# Magnetometer_Channel.net
KiCad netlist of a schematic drawn in Altium Designer
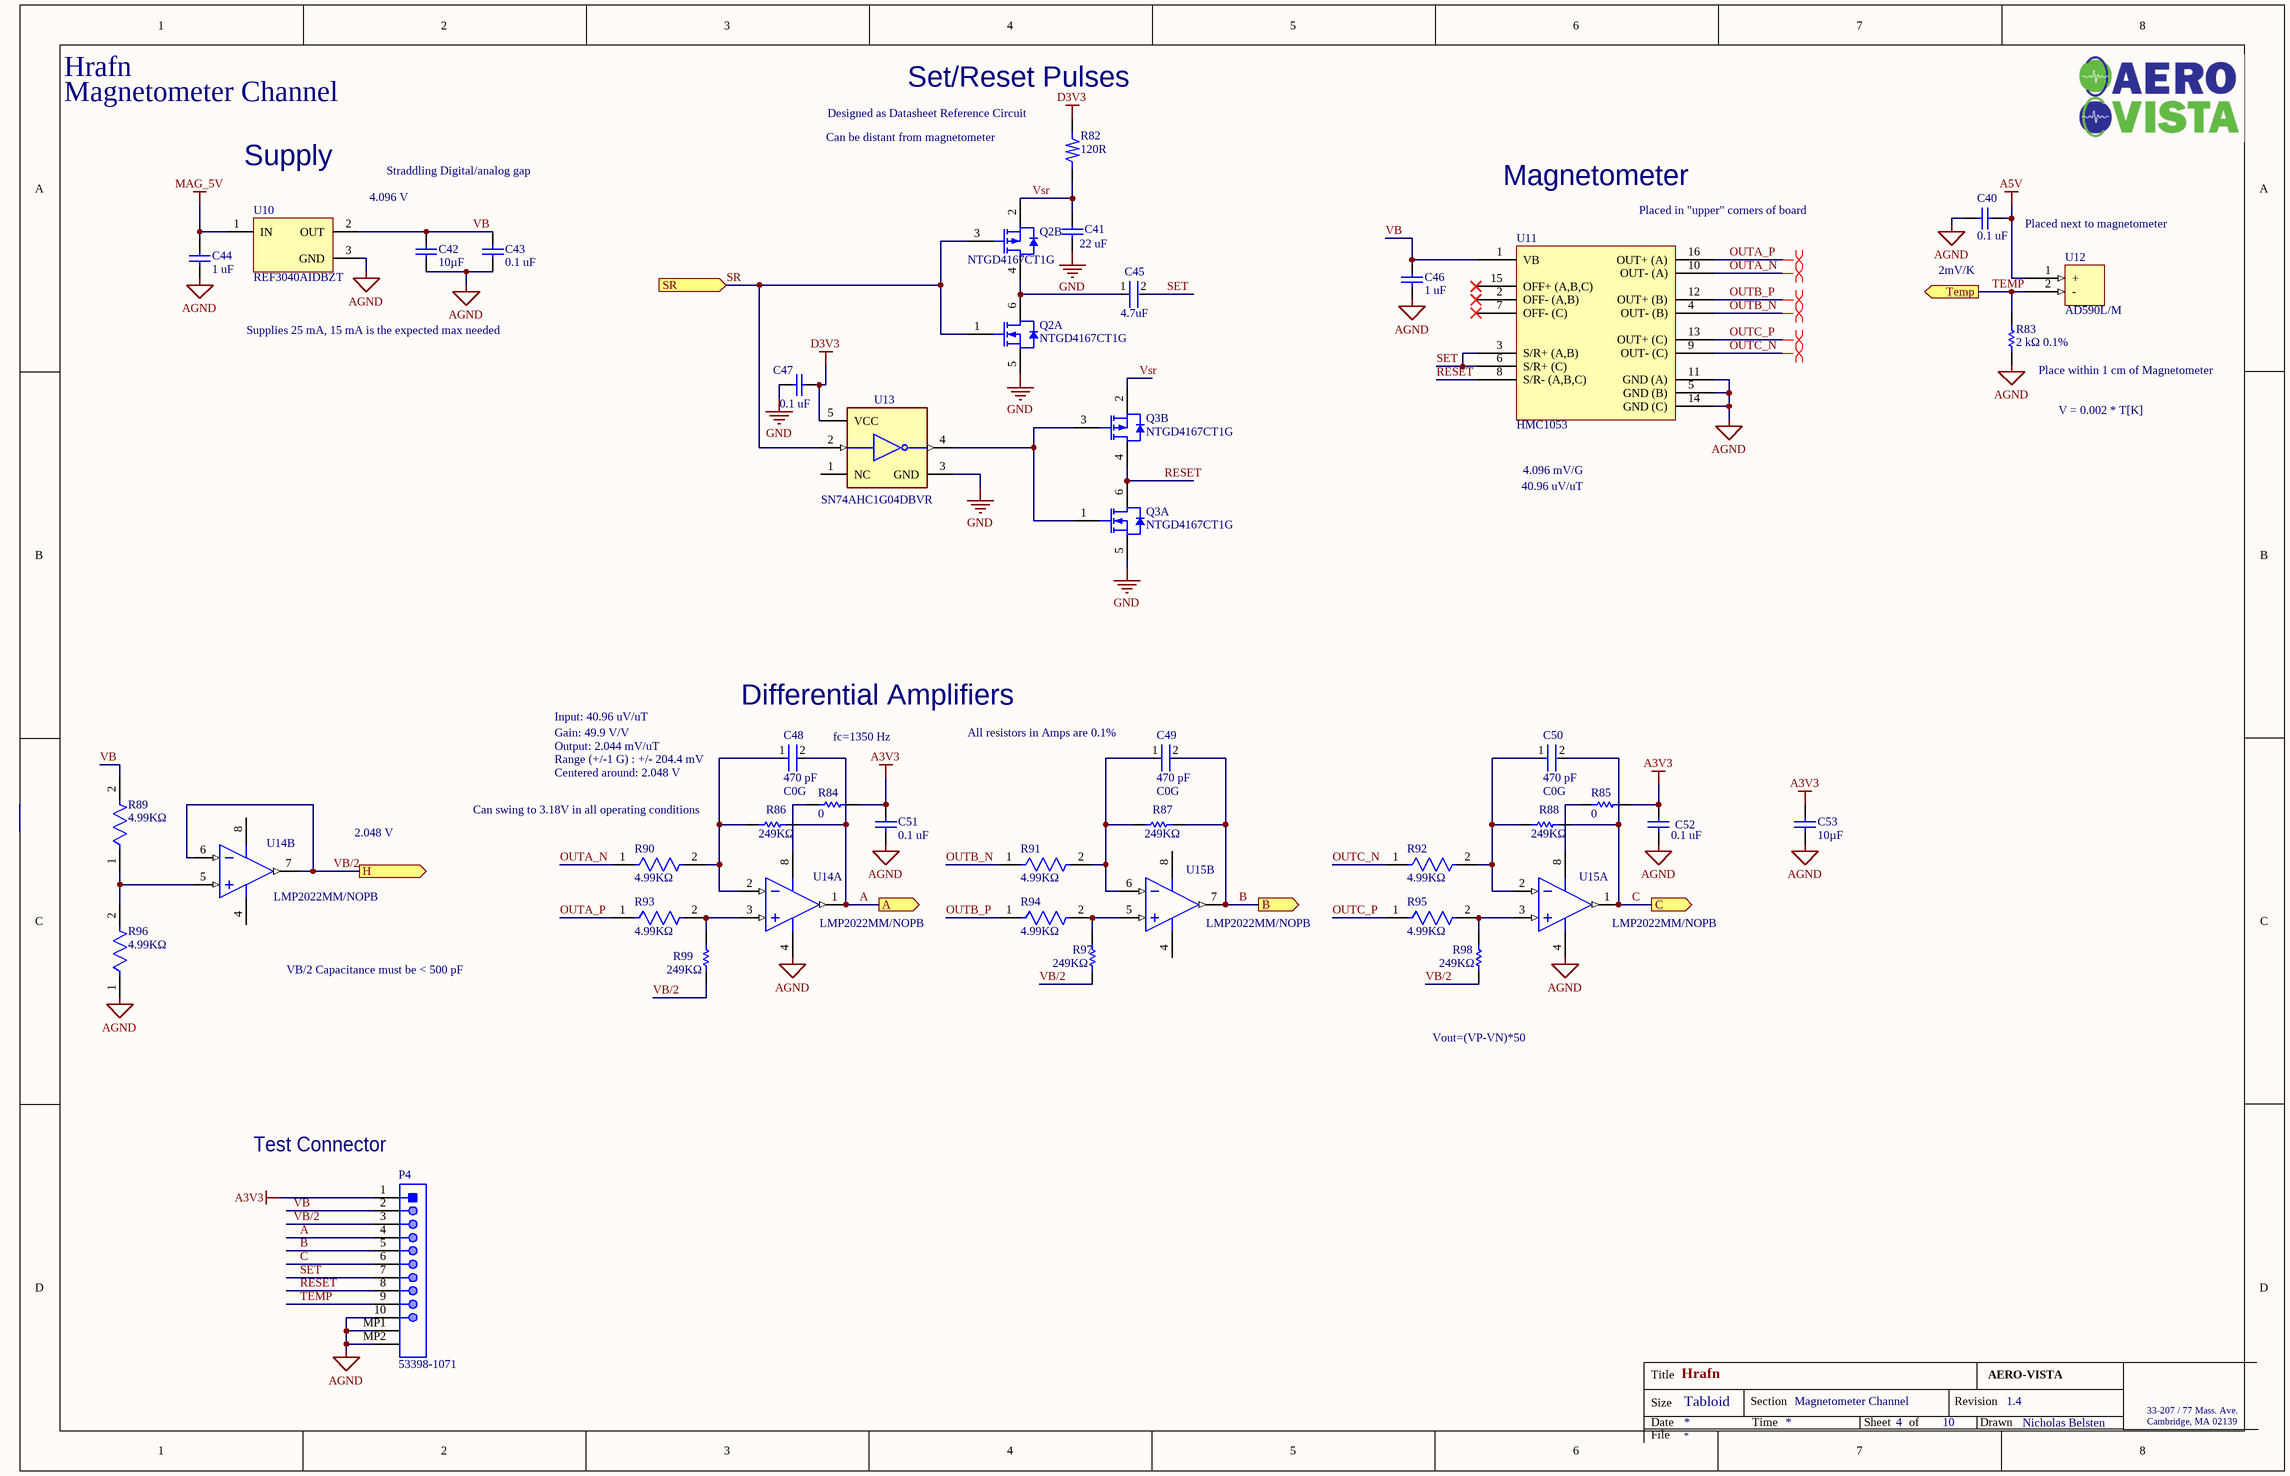
[diagram p0: Magnetometer_Channel.SchDoc]

(export (version "E")
  (design (tool "Eeschema 10.0.6"))
  (components
    (comp (ref "C40")
      (value "0.1 uF")
      (footprint "CAPC0402(1005)60_L")
      (description "CAP 100nF 16V ±5% 0402 (1005 Metric) Thickness 0.6mm SMD")
      (fields (field (name "TOLERANCE") "Â±5%"))
      (libsource (lib "Altium Content Vault") (part "CAP"))
    )
    (comp (ref "C41")
      (value "GRM219R61A226MEA0D")
      (footprint "CAPC2013X95X45LL15T25")
      (fields (field (name "MANUFACTURER") "Murata") (field (name "CAPACITANCE") "22 uF"))
      (libsource (lib "Altium Content Vault") (part "CAP"))
    )
    (comp (ref "C42")
      (value "EMK107BBJ106MA-T")
      (footprint "CAPC1608X100X35LL20T25")
      (description "Chip Capacitor, 10 uF, +/- 20%, 16 V, -55 to 85 degC, 0603 (1608 Metric), RoHS, Tape and Reel")
      (fields
        (field (name "CAPACITANCE") "10µF")
        (field (name "MANUFACTURER") "Taiyo Yuden")
        (field (name "TOLERANCE") "±20%")
      )
      (libsource (lib "Altium Content Vault") (part "CAP-NP-2"))
    )
    (comp (ref "C43")
      (value "0.1 uF")
      (footprint "CAPC0402(1005)60_L")
      (description "CAP 100nF 16V ±5% 0402 (1005 Metric) Thickness 0.6mm SMD")
      (fields (field (name "TOLERANCE") "Â±5%"))
      (libsource (lib "Altium Content Vault") (part "CAP"))
    )
    (comp (ref "C44")
      (value "1 uF")
      (footprint "CAPC1005X60X30NL05T10")
      (fields (field (name "PART NUMBER") "C0402C105M8PACTU") (field (name "MANUFACTURER") "Kemet"))
      (libsource (lib "Altium Content Vault") (part "CAP"))
    )
    (comp (ref "C45")
      (value "GRM188R6YA475KE15D")
      (footprint "FP-GRM188-0_2-IPC_C")
      (description "Chip Multilayer Ceramic Capacitors for General Purpose, 0603, 4.7uF, X5R, 15%, 10%, 35V")
      (fields
        (field (name "CAPACITANCE") "4.7uF")
        (field (name "VOLTAGE") "35V")
        (field (name "TOLERANCE") "10%")
      )
      (libsource (lib "Altium Content Vault") (part "11868f565c42a9108669ba33697ecf6"))
    )
    (comp (ref "C46")
      (value "1 uF")
      (footprint "CAPC1005X60X30NL05T10")
      (fields (field (name "PART NUMBER") "C0402C105M8PACTU") (field (name "MANUFACTURER") "Kemet"))
      (libsource (lib "Altium Content Vault") (part "CAP"))
    )
    (comp (ref "C47")
      (value "0.1 uF")
      (footprint "CAPC0402(1005)60_L")
      (description "CAP 100nF 16V ±5% 0402 (1005 Metric) Thickness 0.6mm SMD")
      (fields (field (name "TOLERANCE") "Â±5%"))
      (libsource (lib "Altium Content Vault") (part "CAP"))
    )
    (comp (ref "C48")
      (value "C0402C471F5GACTU")
      (footprint "FP-C0402-BB-MFG")
      (description "CAP CER 470PF 50V NP0 0402")
      (fields
        (field (name "CAPACITANCE") "470 pF")
        (field (name "MANUFACTURER") "Kemet")
        (field (name "TOLERANCE") "0.01")
        (field (name "TEMPERATURE CHARACTERISTIC") "C0G")
      )
      (libsource (lib "Altium Content Vault") (part "b4654b650e69147ec39a6b967a45e02"))
    )
    (comp (ref "C49")
      (value "C0402C471F5GACTU")
      (footprint "FP-C0402-BB-MFG")
      (description "CAP CER 470PF 50V NP0 0402")
      (fields
        (field (name "CAPACITANCE") "470 pF")
        (field (name "MANUFACTURER") "Kemet")
        (field (name "TOLERANCE") "0.01")
        (field (name "TEMPERATURE CHARACTERISTIC") "C0G")
      )
      (libsource (lib "Altium Content Vault") (part "b4654b650e69147ec39a6b967a45e02"))
    )
    (comp (ref "C50")
      (value "C0402C471F5GACTU")
      (footprint "FP-C0402-BB-MFG")
      (description "CAP CER 470PF 50V NP0 0402")
      (fields
        (field (name "CAPACITANCE") "470 pF")
        (field (name "MANUFACTURER") "Kemet")
        (field (name "TOLERANCE") "0.01")
        (field (name "TEMPERATURE CHARACTERISTIC") "C0G")
      )
      (libsource (lib "Altium Content Vault") (part "b4654b650e69147ec39a6b967a45e02"))
    )
    (comp (ref "C51")
      (value "0.1 uF")
      (footprint "CAPC0402(1005)60_L")
      (description "CAP 100nF 16V ±5% 0402 (1005 Metric) Thickness 0.6mm SMD")
      (fields (field (name "TOLERANCE") "Â±5%"))
      (libsource (lib "Altium Content Vault") (part "CAP"))
    )
    (comp (ref "C52")
      (value "0.1 uF")
      (footprint "CAPC0402(1005)60_L")
      (description "CAP 100nF 16V ±5% 0402 (1005 Metric) Thickness 0.6mm SMD")
      (fields (field (name "TOLERANCE") "Â±5%"))
      (libsource (lib "Altium Content Vault") (part "CAP"))
    )
    (comp (ref "C53")
      (value "EMK107BBJ106MA-T")
      (footprint "CAPC1608X100X35LL20T25")
      (description "Chip Capacitor, 10 uF, +/- 20%, 16 V, -55 to 85 degC, 0603 (1608 Metric), RoHS, Tape and Reel")
      (fields
        (field (name "CAPACITANCE") "10µF")
        (field (name "MANUFACTURER") "Taiyo Yuden")
        (field (name "TOLERANCE") "±20%")
      )
      (libsource (lib "Altium Content Vault") (part "CAP-NP-2"))
    )
    (comp (ref "P4")
      (value "53398-1071")
      (footprint "MOLX-53398-1071_V")
      (description "Male Header, Pitch 1.25 mm, 1 x 10 Position, Height 4.7 mm, -40 to 85 degC, RoHS, Tape and Reel")
      (fields (field (name "MANUFACTURER") "Molex"))
      (libsource (lib "Altium Content Vault") (part "CN-1P-2M-R10"))
    )
    (comp (ref "Q2")
      (value "NTGD4167CT1G")
      (footprint "ONSC-TSOP-6-318G-02_V")
      (description "Power MOSFET, Complementary, 30 V, +2.9 / -2.2 A, 6-Pin TSOP, Pb-Free, Tape and Reel")
      (fields (field (name "MANUFACTURER") "On Semiconductor"))
      (libsource (lib "Altium Content Vault") (part "ONSC-NTGD4167C-TSOP-6-318G-02"))
    )
    (comp (ref "Q3")
      (value "NTGD4167CT1G")
      (footprint "ONSC-TSOP-6-318G-02_V")
      (description "Power MOSFET, Complementary, 30 V, +2.9 / -2.2 A, 6-Pin TSOP, Pb-Free, Tape and Reel")
      (fields (field (name "MANUFACTURER") "On Semiconductor"))
      (libsource (lib "Altium Content Vault") (part "ONSC-NTGD4167C-TSOP-6-318G-02"))
    )
    (comp (ref "R82")
      (value "R")
      (footprint "RESC1608X08L")
      (description "ROHM - ESR03EZPJ121 - RES, AEC-Q200, THICK FILM, 120R, 5%, 0603 ROHS COMPLIANT: YES")
      (fields (field (name "TOLERANCE") "5%") (field (name "RESISTANCE") "120R"))
      (libsource (lib "Hrafn") (part "R"))
    )
    (comp (ref "R83")
      (value "2 kΩ 0.1%")
      (footprint "RESC1005X40X25LL10T10")
      (fields (field (name "MANUFACTURER") "Panasonic") (field (name "PART NUMBER") "ERA-2AEB202X"))
      (libsource (lib "Altium Content Vault") (part "RES"))
    )
    (comp (ref "R84")
      (value "0")
      (footprint "RESC1608X55X25NL10T15")
      (description "Chip Resistor, 0 Ohm, +/- 5%, 0.1 W, -55 to 155 degC, 0603 (1608 Metric), RoHS, Tape and Reel")
      (fields (field (name "TOLERANCE") "5%") (field (name "MANUFACTURER") "Yageo"))
      (libsource (lib "Altium Content Vault") (part "RES-2"))
    )
    (comp (ref "R85")
      (value "0")
      (footprint "RESC1608X55X25NL10T15")
      (description "Chip Resistor, 0 Ohm, +/- 5%, 0.1 W, -55 to 155 degC, 0603 (1608 Metric), RoHS, Tape and Reel")
      (fields (field (name "TOLERANCE") "5%") (field (name "MANUFACTURER") "Yageo"))
      (libsource (lib "Altium Content Vault") (part "RES-2"))
    )
    (comp (ref "R86")
      (value "249KΩ")
      (footprint "RESC1609X55X30LL10T20")
      (fields (field (name "PART NUMBER") "TNPW0603249KBEEA") (field (name "MANUFACTURER") "Vishay Dale"))
      (libsource (lib "Altium Content Vault") (part "RES"))
    )
    (comp (ref "R87")
      (value "249KΩ")
      (footprint "RESC1609X55X30LL10T20")
      (fields (field (name "PART NUMBER") "TNPW0603249KBEEA") (field (name "MANUFACTURER") "Vishay Dale"))
      (libsource (lib "Altium Content Vault") (part "RES"))
    )
    (comp (ref "R88")
      (value "249KΩ")
      (footprint "RESC1609X55X30LL10T20")
      (fields (field (name "PART NUMBER") "TNPW0603249KBEEA") (field (name "MANUFACTURER") "Vishay Dale"))
      (libsource (lib "Altium Content Vault") (part "RES"))
    )
    (comp (ref "R89")
      (value "4.99KΩ")
      (footprint "FP-RT0603-IPC_B")
      (description "RES SMD 4.99K OHM 0.1% 1/10W")
      (fields
        (field (name "MANUFACTURER PART NUMBER") "RT0603BRE074K99L")
        (field (name "OCTOPART") "https://octopart.com/rt0603bre074k99l-yageo-1445653")
      )
      (libsource (lib "Altium Content Vault") (part "1029c3af85768c4190bb7ad29bc67b5"))
    )
    (comp (ref "R90")
      (value "4.99KΩ")
      (footprint "FP-RT0603-MFG")
      (description "RES SMD 4.99K OHM 0.1% 1/10W")
      (fields
        (field (name "MANUFACTURER PART NUMBER") "RT0603BRE074K99L")
        (field (name "OCTOPART") "https://octopart.com/rt0603bre074k99l-yageo-1445653")
      )
      (libsource (lib "Altium Content Vault") (part "1029c3af85768c4190bb7ad29bc67b5"))
    )
    (comp (ref "R91")
      (value "4.99KΩ")
      (footprint "FP-RT0603-IPC_B")
      (description "RES SMD 4.99K OHM 0.1% 1/10W")
      (fields
        (field (name "MANUFACTURER PART NUMBER") "RT0603BRE074K99L")
        (field (name "OCTOPART") "https://octopart.com/rt0603bre074k99l-yageo-1445653")
      )
      (libsource (lib "Altium Content Vault") (part "1029c3af85768c4190bb7ad29bc67b5"))
    )
    (comp (ref "R92")
      (value "4.99KΩ")
      (footprint "FP-RT0603-IPC_B")
      (description "RES SMD 4.99K OHM 0.1% 1/10W")
      (fields
        (field (name "MANUFACTURER PART NUMBER") "RT0603BRE074K99L")
        (field (name "OCTOPART") "https://octopart.com/rt0603bre074k99l-yageo-1445653")
      )
      (libsource (lib "Altium Content Vault") (part "1029c3af85768c4190bb7ad29bc67b5"))
    )
    (comp (ref "R93")
      (value "4.99KΩ")
      (footprint "FP-RT0603-IPC_B")
      (description "RES SMD 4.99K OHM 0.1% 1/10W")
      (fields
        (field (name "MANUFACTURER PART NUMBER") "RT0603BRE074K99L")
        (field (name "OCTOPART") "https://octopart.com/rt0603bre074k99l-yageo-1445653")
      )
      (libsource (lib "Altium Content Vault") (part "1029c3af85768c4190bb7ad29bc67b5"))
    )
    (comp (ref "R94")
      (value "4.99KΩ")
      (footprint "FP-RT0603-IPC_B")
      (description "RES SMD 4.99K OHM 0.1% 1/10W")
      (fields
        (field (name "MANUFACTURER PART NUMBER") "RT0603BRE074K99L")
        (field (name "OCTOPART") "https://octopart.com/rt0603bre074k99l-yageo-1445653")
      )
      (libsource (lib "Altium Content Vault") (part "1029c3af85768c4190bb7ad29bc67b5"))
    )
    (comp (ref "R95")
      (value "4.99KΩ")
      (footprint "FP-RT0603-IPC_B")
      (description "RES SMD 4.99K OHM 0.1% 1/10W")
      (fields
        (field (name "MANUFACTURER PART NUMBER") "RT0603BRE074K99L")
        (field (name "OCTOPART") "https://octopart.com/rt0603bre074k99l-yageo-1445653")
      )
      (libsource (lib "Altium Content Vault") (part "1029c3af85768c4190bb7ad29bc67b5"))
    )
    (comp (ref "R96")
      (value "4.99KΩ")
      (footprint "FP-RT0603-IPC_B")
      (description "RES SMD 4.99K OHM 0.1% 1/10W")
      (fields
        (field (name "MANUFACTURER PART NUMBER") "RT0603BRE074K99L")
        (field (name "OCTOPART") "https://octopart.com/rt0603bre074k99l-yageo-1445653")
      )
      (libsource (lib "Altium Content Vault") (part "1029c3af85768c4190bb7ad29bc67b5"))
    )
    (comp (ref "R97")
      (value "249KΩ")
      (footprint "RESC1609X55X30LL10T20")
      (fields (field (name "PART NUMBER") "TNPW0603249KBEEA") (field (name "MANUFACTURER") "Vishay Dale"))
      (libsource (lib "Altium Content Vault") (part "RES"))
    )
    (comp (ref "R98")
      (value "249KΩ")
      (footprint "RESC1609X55X30LL10T20")
      (fields (field (name "PART NUMBER") "TNPW0603249KBEEA") (field (name "MANUFACTURER") "Vishay Dale"))
      (libsource (lib "Altium Content Vault") (part "RES"))
    )
    (comp (ref "R99")
      (value "249KΩ")
      (footprint "RESC1609X55X30LL10T20")
      (fields (field (name "PART NUMBER") "TNPW0603249KBEEA") (field (name "MANUFACTURER") "Vishay Dale"))
      (libsource (lib "Altium Content Vault") (part "RES"))
    )
    (comp (ref "U10")
      (value "REF3040AIDBZT")
      (footprint "DBZ0003A_N")
      (fields (field (name "MANUFACTURER") "Texas Instruments"))
      (libsource (lib "Altium Content Vault") (part "TI-REF3040DBZ3"))
    )
    (comp (ref "U11") (value "HMC1053") (footprint "LCC16") (libsource (lib "MagEval") (part "HMC1053")))
    (comp (ref "U12") (value "AD590L/M") (footprint "2-FLATPAK") (libsource (lib "Hrafn") (part "AD590L/M")))
    (comp (ref "U13")
      (value "SN74AHC1G04DBVR")
      (footprint "FP-DBV0005A-MFG")
      (description "IC INVERTER 1CH 1-INP SOT23-5")
      (fields
        (field (name "MANUFACTURER") "Texas Instruments")
        (field (name "OCTOPART") "https://octopart.com/sn74ahc1g04dbvr-texas+instruments-464402")
      )
      (libsource (lib "Altium Content Vault") (part "ee34fa538168f64b6768a6ac9278744"))
    )
    (comp (ref "U14")
      (value "LMP2022MM/NOPB")
      (footprint "DGK0008A_L")
      (description "Zero Drift, Low Noise, EMI Hardened Amplifier, 8-pin Mini SOIC, Pb-Free")
      (fields (field (name "MANUFACTURER") "Texas Instruments"))
      (libsource (lib "Altium Content Vault") (part "AMP-OPA-LF353-8"))
    )
    (comp (ref "U15")
      (value "LMP2022MM/NOPB")
      (footprint "DGK0008A_L")
      (description "Zero Drift, Low Noise, EMI Hardened Amplifier, 8-pin Mini SOIC, Pb-Free")
      (fields (field (name "MANUFACTURER") "Texas Instruments"))
      (libsource (lib "Altium Content Vault") (part "AMP-OPA-LF353-8"))
    )
  )
  (nets
    (net (code "1") (name "/A") (class "Default")
      (node (ref "C48") (pin "2") (pinfunction "2_2") (pintype "passive"))
      (node (ref "P4") (pin "4") (pinfunction "4_4") (pintype "passive"))
      (node (ref "R86") (pin "2") (pinfunction "2_2") (pintype "passive"))
      (node (ref "U14") (pin "1") (pinfunction "OUTA_1") (pintype "output"))
    )
    (net (code "2") (name "/B") (class "Default")
      (node (ref "C49") (pin "2") (pinfunction "2_2") (pintype "passive"))
      (node (ref "P4") (pin "5") (pinfunction "5_5") (pintype "passive"))
      (node (ref "R87") (pin "2") (pinfunction "2_2") (pintype "passive"))
      (node (ref "U15") (pin "7") (pinfunction "OUTB_7") (pintype "output"))
    )
    (net (code "3") (name "/C") (class "Default")
      (node (ref "C50") (pin "2") (pinfunction "2_2") (pintype "passive"))
      (node (ref "P4") (pin "6") (pinfunction "6_6") (pintype "passive"))
      (node (ref "R88") (pin "2") (pinfunction "2_2") (pintype "passive"))
      (node (ref "U15") (pin "1") (pinfunction "OUTA_1") (pintype "output"))
    )
    (net (code "4") (name "/OUTA_N") (class "Default")
      (node (ref "R90") (pin "1") (pinfunction "1_1") (pintype "passive"))
      (node (ref "U11") (pin "10") (pinfunction "OUT-_(A)_10") (pintype "power_in"))
    )
    (net (code "5") (name "/OUTA_P") (class "Default")
      (node (ref "R93") (pin "1") (pinfunction "1_1") (pintype "passive"))
      (node (ref "U11") (pin "16") (pinfunction "OUT+_(A)_16") (pintype "passive"))
    )
    (net (code "6") (name "/OUTB_N") (class "Default")
      (node (ref "R91") (pin "1") (pinfunction "1_1") (pintype "passive"))
      (node (ref "U11") (pin "4") (pinfunction "OUT-_(B)_4") (pintype "passive"))
    )
    (net (code "7") (name "/OUTB_P") (class "Default")
      (node (ref "R94") (pin "1") (pinfunction "1_1") (pintype "passive"))
      (node (ref "U11") (pin "12") (pinfunction "OUT+_(B)_12") (pintype "passive"))
    )
    (net (code "8") (name "/OUTC_N") (class "Default")
      (node (ref "R92") (pin "1") (pinfunction "1_1") (pintype "passive"))
      (node (ref "U11") (pin "9") (pinfunction "OUT-_(C)_9") (pintype "passive"))
    )
    (net (code "9") (name "/OUTC_P") (class "Default")
      (node (ref "R95") (pin "1") (pinfunction "1_1") (pintype "passive"))
      (node (ref "U11") (pin "13") (pinfunction "OUT+_(C)_13") (pintype "passive"))
    )
    (net (code "10") (name "/RESET") (class "Default")
      (node (ref "P4") (pin "8") (pinfunction "8_8") (pintype "passive"))
      (node (ref "Q3") (pin "4") (pinfunction "D2_4") (pintype "passive"))
      (node (ref "Q3") (pin "6") (pinfunction "D1_6") (pintype "passive"))
      (node (ref "U11") (pin "8") (pinfunction "S/R-_(A,B,C)_8") (pintype "passive"))
    )
    (net (code "11") (name "/SET") (class "Default")
      (node (ref "C45") (pin "2") (pinfunction "2_2") (pintype "passive"))
      (node (ref "P4") (pin "7") (pinfunction "7_7") (pintype "passive"))
      (node (ref "U11") (pin "3") (pinfunction "S/R+_(A,B)_3") (pintype "passive"))
      (node (ref "U11") (pin "6") (pinfunction "S/R+_(C)_6") (pintype "passive"))
    )
    (net (code "12") (name "/SR") (class "Default")
      (node (ref "Q2") (pin "1") (pinfunction "G1_1") (pintype "passive"))
      (node (ref "Q2") (pin "3") (pinfunction "G2_3") (pintype "passive"))
      (node (ref "U13") (pin "2") (pinfunction "A_2") (pintype "input"))
    )
    (net (code "13") (name "/TEMP") (class "Default")
      (node (ref "P4") (pin "9") (pinfunction "9_9") (pintype "passive"))
      (node (ref "R83") (pin "2") (pinfunction "2_2") (pintype "passive"))
      (node (ref "U12") (pin "2") (pinfunction "-_2") (pintype "input"))
    )
    (net (code "14") (name "/VB") (class "Default")
      (node (ref "C42") (pin "2") (pinfunction "2_2") (pintype "passive"))
      (node (ref "C43") (pin "2") (pinfunction "2_2") (pintype "passive"))
      (node (ref "C46") (pin "2") (pinfunction "2_2") (pintype "passive"))
      (node (ref "P4") (pin "2") (pinfunction "2_2") (pintype "passive"))
      (node (ref "R89") (pin "2") (pinfunction "2_2") (pintype "passive"))
      (node (ref "U10") (pin "2") (pinfunction "OUT_2") (pintype "power_in"))
      (node (ref "U11") (pin "1") (pinfunction "VB_1") (pintype "passive"))
    )
    (net (code "15") (name "/VB{slash}2") (class "Default")
      (node (ref "P4") (pin "3") (pinfunction "3_3") (pintype "passive"))
      (node (ref "R97") (pin "1") (pinfunction "1_1") (pintype "passive"))
      (node (ref "R98") (pin "1") (pinfunction "1_1") (pintype "passive"))
      (node (ref "R99") (pin "1") (pinfunction "1_1") (pintype "passive"))
      (node (ref "U14") (pin "6") (pinfunction "INB-_6") (pintype "input"))
      (node (ref "U14") (pin "7") (pinfunction "OUTB_7") (pintype "output"))
    )
    (net (code "16") (name "/Vsr") (class "Default")
      (node (ref "C41") (pin "2") (pinfunction "2_2") (pintype "passive"))
      (node (ref "Q2") (pin "2") (pinfunction "S2_2") (pintype "passive"))
      (node (ref "Q3") (pin "2") (pinfunction "S2_2") (pintype "passive"))
      (node (ref "R82") (pin "1") (pinfunction "1_1") (pintype "passive"))
    )
    (net (code "17") (name "A3V3") (class "Default")
      (node (ref "C51") (pin "2") (pinfunction "2_2") (pintype "passive"))
      (node (ref "C52") (pin "2") (pinfunction "2_2") (pintype "passive"))
      (node (ref "C53") (pin "2") (pinfunction "2_2") (pintype "passive"))
      (node (ref "P4") (pin "1") (pinfunction "1_1") (pintype "passive"))
      (node (ref "R84") (pin "2") (pinfunction "2_2") (pintype "passive"))
      (node (ref "R85") (pin "2") (pinfunction "2_2") (pintype "passive"))
    )
    (net (code "18") (name "A5V") (class "Default")
      (node (ref "C40") (pin "1") (pinfunction "1_1") (pintype "passive"))
      (node (ref "U12") (pin "1") (pinfunction "+_1") (pintype "input"))
    )
    (net (code "19") (name "AGND") (class "Default")
      (node (ref "C40") (pin "2") (pinfunction "2_2") (pintype "passive"))
      (node (ref "C42") (pin "1") (pinfunction "1_1") (pintype "passive"))
      (node (ref "C43") (pin "1") (pinfunction "1_1") (pintype "passive"))
      (node (ref "C44") (pin "1") (pinfunction "1_1") (pintype "passive"))
      (node (ref "C46") (pin "1") (pinfunction "1_1") (pintype "passive"))
      (node (ref "C51") (pin "1") (pinfunction "1_1") (pintype "passive"))
      (node (ref "C52") (pin "1") (pinfunction "1_1") (pintype "passive"))
      (node (ref "C53") (pin "1") (pinfunction "1_1") (pintype "passive"))
      (node (ref "P4") (pin "10") (pinfunction "10_10") (pintype "passive"))
      (node (ref "P4") (pin "MP1") (pinfunction "MP1_MP1") (pintype "passive"))
      (node (ref "P4") (pin "MP2") (pinfunction "MP2_MP2") (pintype "passive"))
      (node (ref "R83") (pin "1") (pinfunction "1_1") (pintype "passive"))
      (node (ref "R96") (pin "1") (pinfunction "1_1") (pintype "passive"))
      (node (ref "U10") (pin "3") (pinfunction "GND_3") (pintype "power_in"))
      (node (ref "U11") (pin "11") (pinfunction "GND_(A)_11") (pintype "power_in"))
      (node (ref "U11") (pin "14") (pinfunction "GND_(C)_14") (pintype "passive"))
      (node (ref "U11") (pin "5") (pinfunction "GND_(B)_5") (pintype "power_in"))
      (node (ref "U14") (pin "4") (pinfunction "V-_4") (pintype "power_in"))
      (node (ref "U15") (pin "4") (pinfunction "V-_4") (pintype "power_in"))
    )
    (net (code "20") (name "D3V3") (class "Default")
      (node (ref "C47") (pin "2") (pinfunction "2_2") (pintype "passive"))
      (node (ref "R82") (pin "0") (pinfunction "0_0") (pintype "passive"))
      (node (ref "U13") (pin "5") (pinfunction "VCC_5") (pintype "power_in"))
    )
    (net (code "21") (name "GND") (class "Default")
      (node (ref "C41") (pin "1") (pinfunction "1_1") (pintype "passive"))
      (node (ref "C47") (pin "1") (pinfunction "1_1") (pintype "passive"))
      (node (ref "Q2") (pin "5") (pinfunction "S1_5") (pintype "passive"))
      (node (ref "Q3") (pin "5") (pinfunction "S1_5") (pintype "passive"))
      (node (ref "U13") (pin "3") (pinfunction "GND_3") (pintype "power_in"))
    )
    (net (code "22") (name "MAG_5V") (class "Default")
      (node (ref "C44") (pin "2") (pinfunction "2_2") (pintype "passive"))
      (node (ref "U10") (pin "1") (pinfunction "IN_1") (pintype "power_in"))
    )
    (net (code "23") (name "Net-(Q2A-D1)") (class "Default")
      (node (ref "C45") (pin "1") (pinfunction "1_1") (pintype "passive"))
      (node (ref "Q2") (pin "4") (pinfunction "D2_4") (pintype "passive"))
      (node (ref "Q2") (pin "6") (pinfunction "D1_6") (pintype "passive"))
    )
    (net (code "24") (name "Net-(Q3A-G1)") (class "Default")
      (node (ref "Q3") (pin "1") (pinfunction "G1_1") (pintype "passive"))
      (node (ref "Q3") (pin "3") (pinfunction "G2_3") (pintype "passive"))
      (node (ref "U13") (pin "4") (pinfunction "Y_4") (pintype "output"))
    )
    (net (code "25") (name "Net-(U14A-INA+)") (class "Default")
      (node (ref "R93") (pin "2") (pinfunction "2_2") (pintype "passive"))
      (node (ref "R99") (pin "2") (pinfunction "2_2") (pintype "passive"))
      (node (ref "U14") (pin "3") (pinfunction "INA+_3") (pintype "input"))
    )
    (net (code "26") (name "Net-(U14A-INA-)") (class "Default")
      (node (ref "C48") (pin "1") (pinfunction "1_1") (pintype "passive"))
      (node (ref "R86") (pin "1") (pinfunction "1_1") (pintype "passive"))
      (node (ref "R90") (pin "2") (pinfunction "2_2") (pintype "passive"))
      (node (ref "U14") (pin "2") (pinfunction "INA-_2") (pintype "input"))
    )
    (net (code "27") (name "Net-(U14A-V+)") (class "Default")
      (node (ref "R84") (pin "1") (pinfunction "1_1") (pintype "passive"))
      (node (ref "U14") (pin "8") (pinfunction "V+_8") (pintype "power_in"))
    )
    (net (code "28") (name "Net-(U14B-INB+)") (class "Default")
      (node (ref "R89") (pin "1") (pinfunction "1_1") (pintype "passive"))
      (node (ref "R96") (pin "2") (pinfunction "2_2") (pintype "passive"))
      (node (ref "U14") (pin "5") (pinfunction "INB+_5") (pintype "input"))
    )
    (net (code "29") (name "Net-(U15A-INA+)") (class "Default")
      (node (ref "R95") (pin "2") (pinfunction "2_2") (pintype "passive"))
      (node (ref "R98") (pin "2") (pinfunction "2_2") (pintype "passive"))
      (node (ref "U15") (pin "3") (pinfunction "INA+_3") (pintype "input"))
    )
    (net (code "30") (name "Net-(U15A-INA-)") (class "Default")
      (node (ref "C50") (pin "1") (pinfunction "1_1") (pintype "passive"))
      (node (ref "R88") (pin "1") (pinfunction "1_1") (pintype "passive"))
      (node (ref "R92") (pin "2") (pinfunction "2_2") (pintype "passive"))
      (node (ref "U15") (pin "2") (pinfunction "INA-_2") (pintype "input"))
    )
    (net (code "31") (name "Net-(U15A-V+)") (class "Default")
      (node (ref "R85") (pin "1") (pinfunction "1_1") (pintype "passive"))
      (node (ref "U15") (pin "8") (pinfunction "V+_8") (pintype "power_in"))
    )
    (net (code "32") (name "Net-(U15B-INB+)") (class "Default")
      (node (ref "R94") (pin "2") (pinfunction "2_2") (pintype "passive"))
      (node (ref "R97") (pin "2") (pinfunction "2_2") (pintype "passive"))
      (node (ref "U15") (pin "5") (pinfunction "INB+_5") (pintype "input"))
    )
    (net (code "33") (name "Net-(U15B-INB-)") (class "Default")
      (node (ref "C49") (pin "1") (pinfunction "1_1") (pintype "passive"))
      (node (ref "R87") (pin "1") (pinfunction "1_1") (pintype "passive"))
      (node (ref "R91") (pin "2") (pinfunction "2_2") (pintype "passive"))
      (node (ref "U15") (pin "6") (pinfunction "INB-_6") (pintype "input"))
    )
    (net (code "34") (name "unconnected-(U11-OFF+_(A,B,C)-Pad15)") (class "Default")
      (node (ref "U11") (pin "15") (pinfunction "OFF+_(A,B,C)_15") (pintype "passive+no_connect"))
    )
    (net (code "35") (name "unconnected-(U11-OFF-_(A,B)-Pad2)") (class "Default")
      (node (ref "U11") (pin "2") (pinfunction "OFF-_(A,B)_2") (pintype "passive+no_connect"))
    )
    (net (code "36") (name "unconnected-(U11-OFF-_(C)-Pad7)") (class "Default")
      (node (ref "U11") (pin "7") (pinfunction "OFF-_(C)_7") (pintype "passive+no_connect"))
    )
    (net (code "37") (name "unconnected-(U13-NC-Pad1)") (class "Default")
      (node (ref "U13") (pin "1") (pinfunction "NC_1") (pintype "passive"))
    )
    (net (code "38") (name "unconnected-(U14B-V+-Pad8)") (class "Default")
      (node (ref "U14") (pin "8") (pinfunction "V+_8") (pintype "power_in"))
    )
    (net (code "39") (name "unconnected-(U14B-V--Pad4)") (class "Default")
      (node (ref "U14") (pin "4") (pinfunction "V-_4") (pintype "power_in"))
    )
    (net (code "40") (name "unconnected-(U15B-V+-Pad8)") (class "Default")
      (node (ref "U15") (pin "8") (pinfunction "V+_8") (pintype "power_in"))
    )
    (net (code "41") (name "unconnected-(U15B-V--Pad4)") (class "Default")
      (node (ref "U15") (pin "4") (pinfunction "V-_4") (pintype "power_in"))
    )
  )
)
